# Sheet1.net
KiCad netlist of a schematic drawn in Altium Designer
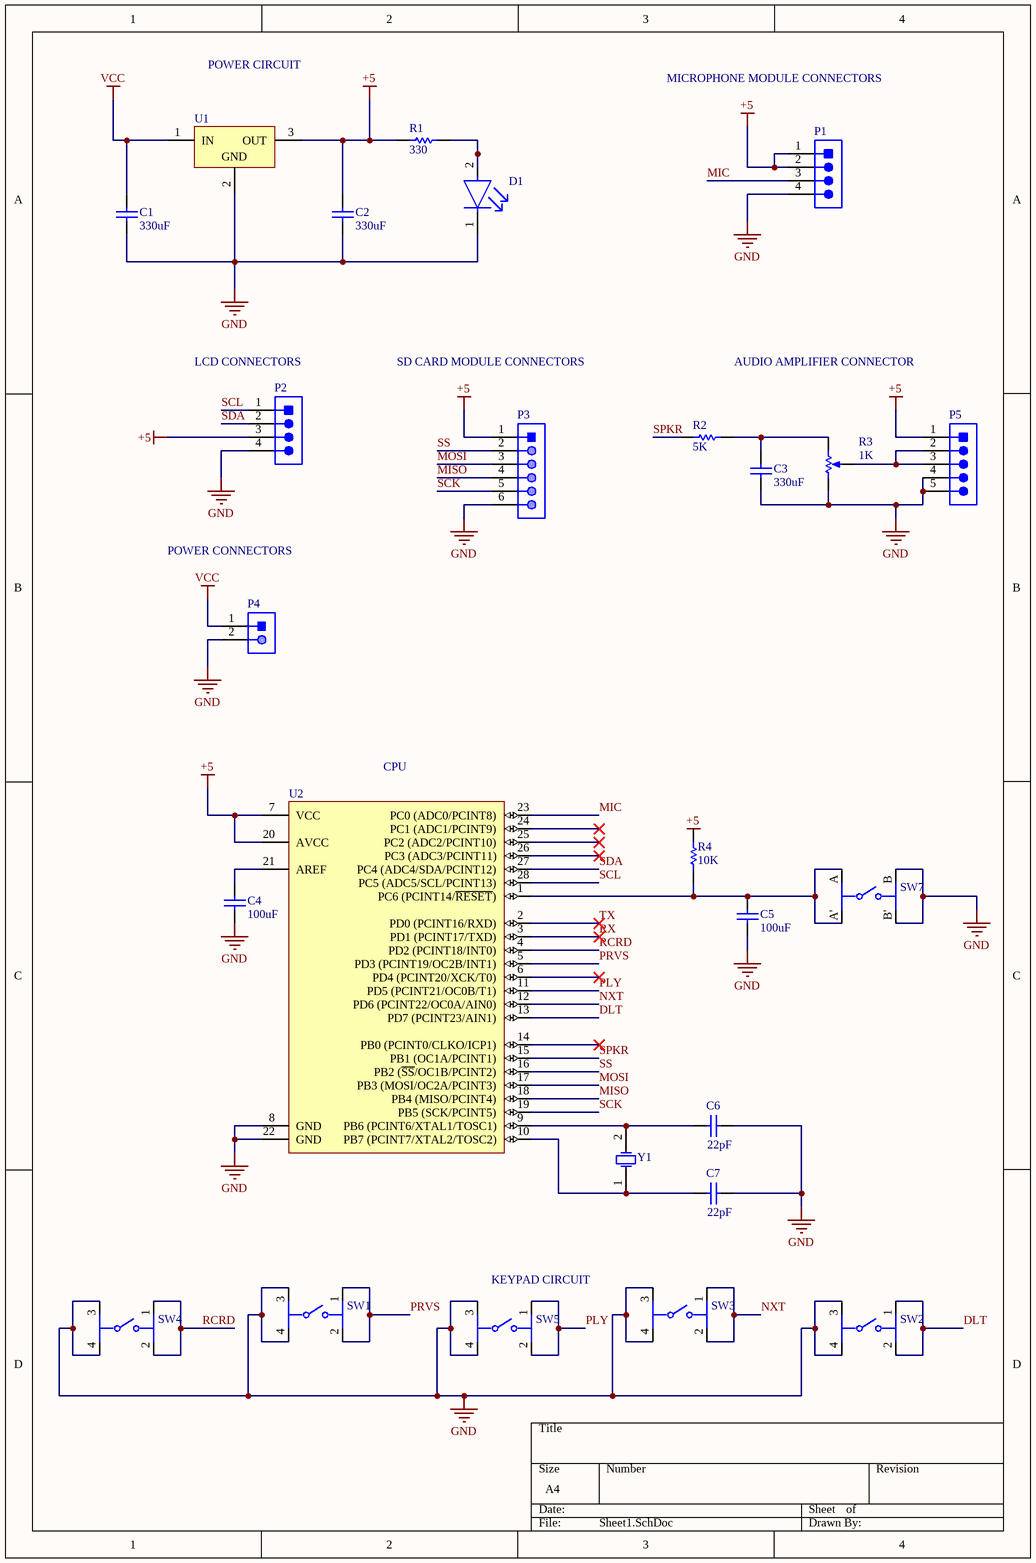
[diagram p0: Sheet1.SchDoc]

(export (version "E")
  (design (tool "Eeschema 10.0.6"))
  (components
    (comp (ref "C1")
      (value "330uF")
      (footprint "RAD-0.3")
      (description "Capacitor")
      (fields (field (name "PUBLISHER") "Altium Limited"))
      (libsource (lib "Miscellaneous Devices") (part "Cap"))
    )
    (comp (ref "C2")
      (value "330uF")
      (footprint "RAD-0.3")
      (description "Capacitor")
      (fields (field (name "PUBLISHER") "Altium Limited"))
      (libsource (lib "Miscellaneous Devices") (part "Cap"))
    )
    (comp (ref "C3")
      (value "330uF")
      (footprint "RAD-0.3")
      (description "Capacitor")
      (fields (field (name "PUBLISHER") "Altium Limited"))
      (libsource (lib "Miscellaneous Devices") (part "Cap"))
    )
    (comp (ref "C4")
      (value "~")
      (footprint "KEMT-C330C105M5U5TA")
      (description "Ceramic Capacitor, 1 uF, +/- 20%, 50 V, -10 to 85 degC, 2-Pin THD, RoHS, Bulk")
      (fields
        (field (name "TOLERANCE") "±20%")
        (field (name "CAPACITANCE") "100uF")
        (field (name "MANUFACTURER") "Kemet")
      )
      (libsource (lib "Altium Content Vault") (part "CAP-NP-2"))
    )
    (comp (ref "C5")
      (value "C330C105M5U5TA")
      (footprint "KEMT-C330C105M5U5TA")
      (description "Ceramic Capacitor, 1 uF, +/- 20%, 50 V, -10 to 85 degC, 2-Pin THD, RoHS, Bulk")
      (fields
        (field (name "TOLERANCE") "±20%")
        (field (name "CAPACITANCE") "100uF")
        (field (name "MANUFACTURER") "Kemet")
      )
      (libsource (lib "Altium Content Vault") (part "CAP-NP-2"))
    )
    (comp (ref "C6")
      (value "C330C105M5U5TA")
      (footprint "KEMT-C330C105M5U5TA")
      (description "Ceramic Capacitor, 1 uF, +/- 20%, 50 V, -10 to 85 degC, 2-Pin THD, RoHS, Bulk")
      (fields
        (field (name "TOLERANCE") "±20%")
        (field (name "CAPACITANCE") "22pF")
        (field (name "MANUFACTURER") "Kemet")
      )
      (libsource (lib "Altium Content Vault") (part "CAP-NP-2"))
    )
    (comp (ref "C7")
      (value "C330C105M5U5TA")
      (footprint "KEMT-C330C105M5U5TA")
      (description "Ceramic Capacitor, 1 uF, +/- 20%, 50 V, -10 to 85 degC, 2-Pin THD, RoHS, Bulk")
      (fields
        (field (name "TOLERANCE") "±20%")
        (field (name "CAPACITANCE") "22pF")
        (field (name "MANUFACTURER") "Kemet")
      )
      (libsource (lib "Altium Content Vault") (part "CAP-NP-2"))
    )
    (comp (ref "D1")
      (value "HLMP-1719")
      (footprint "FP-HLMP-1719-MFG")
      (description "LED YELLOW DIFFUSED T-1 T/H")
      (fields
        (field (name "MANUFACTURER") "Broadcom")
        (field (name "OCTOPART") "https://octopart.com/hlmp-1719-broadcom-71130405")
      )
      (libsource (lib "Altium Content Vault") (part "8706943c75ba83719d021d2fdc84c58"))
    )
    (comp (ref "P1")
      (value "640456-4")
      (footprint "TECO-640456-4")
      (description "Male Header, Pitch 2.54 mm, 1 x 4 Position, Height 10.03 mm, Tail Length 3.56 mm, RoHS, Bulk")
      (fields (field (name "MANUFACTURER") "TE Connectivity"))
      (libsource (lib "Altium Content Vault") (part "CN-1P-M-R4"))
    )
    (comp (ref "P2")
      (value "640456-4")
      (footprint "TECO-640456-4")
      (description "Male Header, Pitch 2.54 mm, 1 x 4 Position, Height 10.03 mm, Tail Length 3.56 mm, RoHS, Bulk")
      (fields (field (name "MANUFACTURER") "TE Connectivity"))
      (libsource (lib "Altium Content Vault") (part "CN-1P-M-R4"))
    )
    (comp (ref "P3")
      (value "66200611122")
      (footprint "66200611122")
      (description "THT Male Header WR-MPC3, Vertical, Single Row, pitch 3 mm, 6 pins")
      (fields (field (name "MANUFACTURER") "Wurth Elektronik") (field (name "PUBLISHER") "WurthElektronik"))
      (libsource (lib "Altium Content Vault") (part "WE-CN-1P-M-R6"))
    )
    (comp (ref "P4")
      (value "61900211121")
      (footprint "61900211121")
      (description "Male Locking Header WR-WTB, THT, Vertical, pitch 2.54 mm, 1 x 2 position")
      (fields (field (name "MANUFACTURER") "Wurth Elektronik") (field (name "PUBLISHER") "WurthElektronik"))
      (libsource (lib "Altium Content Vault") (part "WE-CN-1P-M-R2"))
    )
    (comp (ref "P5")
      (value "640456-5")
      (footprint "TECO-640456-5")
      (fields (field (name "MANUFACTURER") "TE Connectivity"))
      (libsource (lib "Altium Content Vault") (part "CN-1P-M-R5"))
    )
    (comp (ref "R1")
      (value "330")
      (footprint "AXIAL-0.3")
      (description "Resistor")
      (fields (field (name "PUBLISHER") "Altium Limited"))
      (libsource (lib "Miscellaneous Devices") (part "Res1"))
    )
    (comp (ref "R2")
      (value "5K")
      (footprint "AXIAL-0.3")
      (description "Resistor")
      (fields (field (name "PUBLISHER") "Altium Limited"))
      (libsource (lib "Miscellaneous Devices") (part "Res1"))
    )
    (comp (ref "R3")
      (value "1K")
      (footprint "VR5")
      (description "Potentiometer")
      (fields (field (name "PUBLISHER") "Altium Limited"))
      (libsource (lib "Miscellaneous Devices") (part "RPot"))
    )
    (comp (ref "R4")
      (value "10K")
      (footprint "AXIAL-0.3")
      (description "Resistor")
      (fields (field (name "PUBLISHER") "Altium Limited"))
      (libsource (lib "Miscellaneous Devices") (part "Res1"))
    )
    (comp (ref "SW1")
      (value "FSM100")
      (footprint "FP-FSM100-MFG")
      (description "SWITCH TACTILE SPST-NO 0.05A 24V")
      (libsource (lib "Altium Content Vault") (part "1adf0dd01260c80cf25a44bfd6b99ba"))
    )
    (comp (ref "SW2")
      (value "FSM100")
      (footprint "FP-FSM100-MFG")
      (description "SWITCH TACTILE SPST-NO 0.05A 24V")
      (libsource (lib "Altium Content Vault") (part "1adf0dd01260c80cf25a44bfd6b99ba"))
    )
    (comp (ref "SW3")
      (value "FSM100")
      (footprint "FP-FSM100-MFG")
      (description "SWITCH TACTILE SPST-NO 0.05A 24V")
      (libsource (lib "Altium Content Vault") (part "1adf0dd01260c80cf25a44bfd6b99ba"))
    )
    (comp (ref "SW4")
      (value "FSM100")
      (footprint "FP-FSM100-MFG")
      (description "SWITCH TACTILE SPST-NO 0.05A 24V")
      (libsource (lib "Altium Content Vault") (part "1adf0dd01260c80cf25a44bfd6b99ba"))
    )
    (comp (ref "SW5")
      (value "FSM100")
      (footprint "FP-FSM100-MFG")
      (description "SWITCH TACTILE SPST-NO 0.05A 24V")
      (libsource (lib "Altium Content Vault") (part "1adf0dd01260c80cf25a44bfd6b99ba"))
    )
    (comp (ref "SW7")
      (value "EVQ-PAG07K")
      (footprint "FP-EVQ-PAG07K-MFG")
      (description "SWITCH TACTILE SPST-NO 0.02A 15V")
      (libsource (lib "Altium Content Vault") (part "75038bc65b1af1a6bd057da08483287"))
    )
    (comp (ref "U1")
      (value "L7805CV")
      (footprint "TO220")
      (description "Positive Voltage Regulator, 5V, 3-Pin TO-220")
      (libsource (lib "Altium Content Vault") (part "PM-REG-L4940-SIL3"))
    )
    (comp (ref "U2")
      (value "ATmega328P-PU")
      (footprint "28P3")
      (libsource (lib "Altium Content Vault") (part "MC-8B-ATM48-IL28"))
    )
    (comp (ref "Y1")
      (value "XTAL")
      (footprint "R38")
      (description "Crystal Oscillator")
      (fields (field (name "PUBLISHER") "Altium Limited"))
      (libsource (lib "Miscellaneous Devices") (part "XTAL"))
    )
  )
  (nets
    (net (code "1") (name "+5") (class "Default")
      (node (ref "C2") (pin "2") (pinfunction "2_2") (pintype "passive"))
      (node (ref "P1") (pin "1") (pinfunction "1_1") (pintype "passive"))
      (node (ref "P1") (pin "2") (pinfunction "2_2") (pintype "passive"))
      (node (ref "P2") (pin "3") (pinfunction "3_3") (pintype "passive"))
      (node (ref "P3") (pin "1") (pinfunction "1_1") (pintype "passive"))
      (node (ref "P5") (pin "1") (pinfunction "DTR_1") (pintype "passive"))
      (node (ref "R1") (pin "1") (pinfunction "1_1") (pintype "passive"))
      (node (ref "U1") (pin "3") (pinfunction "OUT_3") (pintype "power_in"))
      (node (ref "U2") (pin "20") (pinfunction "AVCC_20") (pintype "power_in"))
      (node (ref "U2") (pin "7") (pinfunction "VCC_7") (pintype "power_in"))
    )
    (net (code "2") (name "/DLT") (class "Default")
      (node (ref "SW2") (pin "1") (pinfunction "1_1") (pintype "passive"))
      (node (ref "SW2") (pin "2") (pinfunction "2_2") (pintype "passive"))
      (node (ref "U2") (pin "13") (pinfunction "PD7_(PCINT23/AIN1)_13") (pintype "bidirectional"))
    )
    (net (code "3") (name "/MIC") (class "Default")
      (node (ref "P1") (pin "3") (pinfunction "3_3") (pintype "passive"))
      (node (ref "U2") (pin "23") (pinfunction "PC0_(ADC0/PCINT8)_23") (pintype "bidirectional"))
    )
    (net (code "4") (name "/MISO") (class "Default")
      (node (ref "P3") (pin "4") (pinfunction "4_4") (pintype "passive"))
      (node (ref "U2") (pin "18") (pinfunction "PB4_(MISO/PCINT4)_18") (pintype "bidirectional"))
    )
    (net (code "5") (name "/MOSI") (class "Default")
      (node (ref "P3") (pin "3") (pinfunction "3_3") (pintype "passive"))
      (node (ref "U2") (pin "17") (pinfunction "PB3_(MOSI/OC2A/PCINT3)_17") (pintype "bidirectional"))
    )
    (net (code "6") (name "/NXT") (class "Default")
      (node (ref "SW3") (pin "1") (pinfunction "1_1") (pintype "passive"))
      (node (ref "SW3") (pin "2") (pinfunction "2_2") (pintype "passive"))
      (node (ref "U2") (pin "12") (pinfunction "PD6_(PCINT22/OC0A/AIN0)_12") (pintype "bidirectional"))
    )
    (net (code "7") (name "/PLY") (class "Default")
      (node (ref "SW5") (pin "1") (pinfunction "1_1") (pintype "passive"))
      (node (ref "SW5") (pin "2") (pinfunction "2_2") (pintype "passive"))
      (node (ref "U2") (pin "11") (pinfunction "PD5_(PCINT21/OC0B/T1)_11") (pintype "bidirectional"))
    )
    (net (code "8") (name "/PRVS") (class "Default")
      (node (ref "SW1") (pin "1") (pinfunction "1_1") (pintype "passive"))
      (node (ref "SW1") (pin "2") (pinfunction "2_2") (pintype "passive"))
      (node (ref "U2") (pin "5") (pinfunction "PD3_(PCINT19/OC2B/INT1)_5") (pintype "bidirectional"))
    )
    (net (code "9") (name "/RCRD") (class "Default")
      (node (ref "SW4") (pin "1") (pinfunction "1_1") (pintype "passive"))
      (node (ref "SW4") (pin "2") (pinfunction "2_2") (pintype "passive"))
      (node (ref "U2") (pin "4") (pinfunction "PD2_(PCINT18/INT0)_4") (pintype "bidirectional"))
    )
    (net (code "10") (name "/RX") (class "Default")
      (node (ref "U2") (pin "3") (pinfunction "PD1_(PCINT17/TXD)_3") (pintype "bidirectional+no_connect"))
    )
    (net (code "11") (name "/SCK") (class "Default")
      (node (ref "P3") (pin "5") (pinfunction "5_5") (pintype "passive"))
      (node (ref "U2") (pin "19") (pinfunction "PB5_(SCK/PCINT5)_19") (pintype "bidirectional"))
    )
    (net (code "12") (name "/SCL") (class "Default")
      (node (ref "P2") (pin "1") (pinfunction "1_1") (pintype "passive"))
      (node (ref "U2") (pin "28") (pinfunction "PC5_(ADC5/SCL/PCINT13)_28") (pintype "bidirectional"))
    )
    (net (code "13") (name "/SDA") (class "Default")
      (node (ref "P2") (pin "2") (pinfunction "2_2") (pintype "passive"))
      (node (ref "U2") (pin "27") (pinfunction "PC4_(ADC4/SDA/PCINT12)_27") (pintype "bidirectional"))
    )
    (net (code "14") (name "/SPKR") (class "Default")
      (node (ref "R2") (pin "2") (pinfunction "2_2") (pintype "passive"))
      (node (ref "U2") (pin "15") (pinfunction "PB1_(OC1A/PCINT1)_15") (pintype "bidirectional"))
    )
    (net (code "15") (name "/SS") (class "Default")
      (node (ref "P3") (pin "2") (pinfunction "2_2") (pintype "passive"))
      (node (ref "U2") (pin "16") (pinfunction "PB2_(~{SS}/OC1B/PCINT2)_16") (pintype "bidirectional"))
    )
    (net (code "16") (name "/TX") (class "Default")
      (node (ref "U2") (pin "2") (pinfunction "PD0_(PCINT16/RXD)_2") (pintype "bidirectional+no_connect"))
    )
    (net (code "17") (name "GND") (class "Default")
      (node (ref "C1") (pin "1") (pinfunction "1_1") (pintype "passive"))
      (node (ref "C2") (pin "1") (pinfunction "1_1") (pintype "passive"))
      (node (ref "C3") (pin "1") (pinfunction "1_1") (pintype "passive"))
      (node (ref "C4") (pin "1") (pinfunction "1_1") (pintype "passive"))
      (node (ref "C5") (pin "1") (pinfunction "1_1") (pintype "passive"))
      (node (ref "C6") (pin "2") (pinfunction "2_2") (pintype "passive"))
      (node (ref "C7") (pin "2") (pinfunction "2_2") (pintype "passive"))
      (node (ref "D1") (pin "1") (pinfunction "C_1") (pintype "passive"))
      (node (ref "P1") (pin "4") (pinfunction "4_4") (pintype "passive"))
      (node (ref "P2") (pin "4") (pinfunction "4_4") (pintype "passive"))
      (node (ref "P3") (pin "6") (pinfunction "6_6") (pintype "passive"))
      (node (ref "P4") (pin "2") (pinfunction "2_2") (pintype "passive"))
      (node (ref "P5") (pin "4") (pinfunction "VCC_4") (pintype "passive"))
      (node (ref "P5") (pin "5") (pinfunction "CTS_5") (pintype "passive"))
      (node (ref "R3") (pin "1") (pinfunction "TOP_1") (pintype "passive"))
      (node (ref "SW1") (pin "3") (pinfunction "3_3") (pintype "passive"))
      (node (ref "SW1") (pin "4") (pinfunction "4_4") (pintype "passive"))
      (node (ref "SW2") (pin "3") (pinfunction "3_3") (pintype "passive"))
      (node (ref "SW2") (pin "4") (pinfunction "4_4") (pintype "passive"))
      (node (ref "SW3") (pin "3") (pinfunction "3_3") (pintype "passive"))
      (node (ref "SW3") (pin "4") (pinfunction "4_4") (pintype "passive"))
      (node (ref "SW4") (pin "3") (pinfunction "3_3") (pintype "passive"))
      (node (ref "SW4") (pin "4") (pinfunction "4_4") (pintype "passive"))
      (node (ref "SW5") (pin "3") (pinfunction "3_3") (pintype "passive"))
      (node (ref "SW5") (pin "4") (pinfunction "4_4") (pintype "passive"))
      (node (ref "SW7") (pin "B") (pinfunction "B_B") (pintype "passive"))
      (node (ref "SW7") (pin "B'") (pinfunction "B'_B'") (pintype "passive"))
      (node (ref "U1") (pin "2") (pinfunction "GND_2") (pintype "power_in"))
      (node (ref "U2") (pin "22") (pinfunction "GND_22") (pintype "power_in"))
      (node (ref "U2") (pin "8") (pinfunction "GND_8") (pintype "power_in"))
    )
    (net (code "18") (name "Net-(D1-A)") (class "Default")
      (node (ref "D1") (pin "2") (pinfunction "A_2") (pintype "passive"))
      (node (ref "R1") (pin "2") (pinfunction "2_2") (pintype "passive"))
    )
    (net (code "19") (name "Net-(P5-RXI)") (class "Default")
      (node (ref "P5") (pin "2") (pinfunction "RXI_2") (pintype "passive"))
      (node (ref "P5") (pin "3") (pinfunction "TXO_3") (pintype "passive"))
      (node (ref "R3") (pin "3") (pinfunction "TAP_3") (pintype "passive"))
    )
    (net (code "20") (name "Net-(R3-BOT)") (class "Default")
      (node (ref "C3") (pin "2") (pinfunction "2_2") (pintype "passive"))
      (node (ref "R2") (pin "1") (pinfunction "1_1") (pintype "passive"))
      (node (ref "R3") (pin "2") (pinfunction "BOT_2") (pintype "passive"))
    )
    (net (code "21") (name "Net-(U2-AREF)") (class "Default")
      (node (ref "C4") (pin "2") (pinfunction "2_2") (pintype "passive"))
      (node (ref "U2") (pin "21") (pinfunction "AREF_21") (pintype "power_in"))
    )
    (net (code "22") (name "Net-(U2-PB6_(PCINT6{slash}XTAL1{slash}TOSC1))") (class "Default")
      (node (ref "C6") (pin "1") (pinfunction "1_1") (pintype "passive"))
      (node (ref "U2") (pin "9") (pinfunction "PB6_(PCINT6/XTAL1/TOSC1)_9") (pintype "bidirectional"))
      (node (ref "Y1") (pin "2") (pinfunction "OSC2_2") (pintype "passive"))
    )
    (net (code "23") (name "Net-(U2-PB7_(PCINT7{slash}XTAL2{slash}TOSC2))") (class "Default")
      (node (ref "C7") (pin "1") (pinfunction "1_1") (pintype "passive"))
      (node (ref "U2") (pin "10") (pinfunction "PB7_(PCINT7/XTAL2/TOSC2)_10") (pintype "bidirectional"))
      (node (ref "Y1") (pin "1") (pinfunction "OSC1_1") (pintype "passive"))
    )
    (net (code "24") (name "Net-(U2-PC6_(PCINT14{slash}~{RESET}))") (class "Default")
      (node (ref "C5") (pin "2") (pinfunction "2_2") (pintype "passive"))
      (node (ref "R4") (pin "2") (pinfunction "2_2") (pintype "passive"))
      (node (ref "SW7") (pin "A") (pinfunction "A_A") (pintype "passive"))
      (node (ref "SW7") (pin "A'") (pinfunction "A'_A'") (pintype "passive"))
      (node (ref "U2") (pin "1") (pinfunction "PC6_(PCINT14/~{RESET})_1") (pintype "bidirectional"))
    )
    (net (code "25") (name "VCC") (class "Default")
      (node (ref "C1") (pin "2") (pinfunction "2_2") (pintype "passive"))
      (node (ref "P4") (pin "1") (pinfunction "1_1") (pintype "passive"))
      (node (ref "U1") (pin "1") (pinfunction "IN_1") (pintype "power_in"))
    )
    (net (code "26") (name "unconnected-(R4-Pad1)") (class "Default")
      (node (ref "R4") (pin "1") (pinfunction "1_1") (pintype "passive"))
    )
    (net (code "27") (name "unconnected-(U2-PB0_(PCINT0{slash}CLKO{slash}ICP1)-Pad14)") (class "Default")
      (node (ref "U2") (pin "14") (pinfunction "PB0_(PCINT0/CLKO/ICP1)_14") (pintype "bidirectional+no_connect"))
    )
    (net (code "28") (name "unconnected-(U2-PC1_(ADC1{slash}PCINT9)-Pad24)") (class "Default")
      (node (ref "U2") (pin "24") (pinfunction "PC1_(ADC1/PCINT9)_24") (pintype "bidirectional+no_connect"))
    )
    (net (code "29") (name "unconnected-(U2-PC2_(ADC2{slash}PCINT10)-Pad25)") (class "Default")
      (node (ref "U2") (pin "25") (pinfunction "PC2_(ADC2/PCINT10)_25") (pintype "bidirectional+no_connect"))
    )
    (net (code "30") (name "unconnected-(U2-PC3_(ADC3{slash}PCINT11)-Pad26)") (class "Default")
      (node (ref "U2") (pin "26") (pinfunction "PC3_(ADC3/PCINT11)_26") (pintype "bidirectional+no_connect"))
    )
    (net (code "31") (name "unconnected-(U2-PD4_(PCINT20{slash}XCK{slash}T0)-Pad6)") (class "Default")
      (node (ref "U2") (pin "6") (pinfunction "PD4_(PCINT20/XCK/T0)_6") (pintype "bidirectional+no_connect"))
    )
  )
)
